# Stockwaage_Schematic_EasyEDA_ver_1_7.net
KiCad netlist of a schematic drawn in EasyEDA
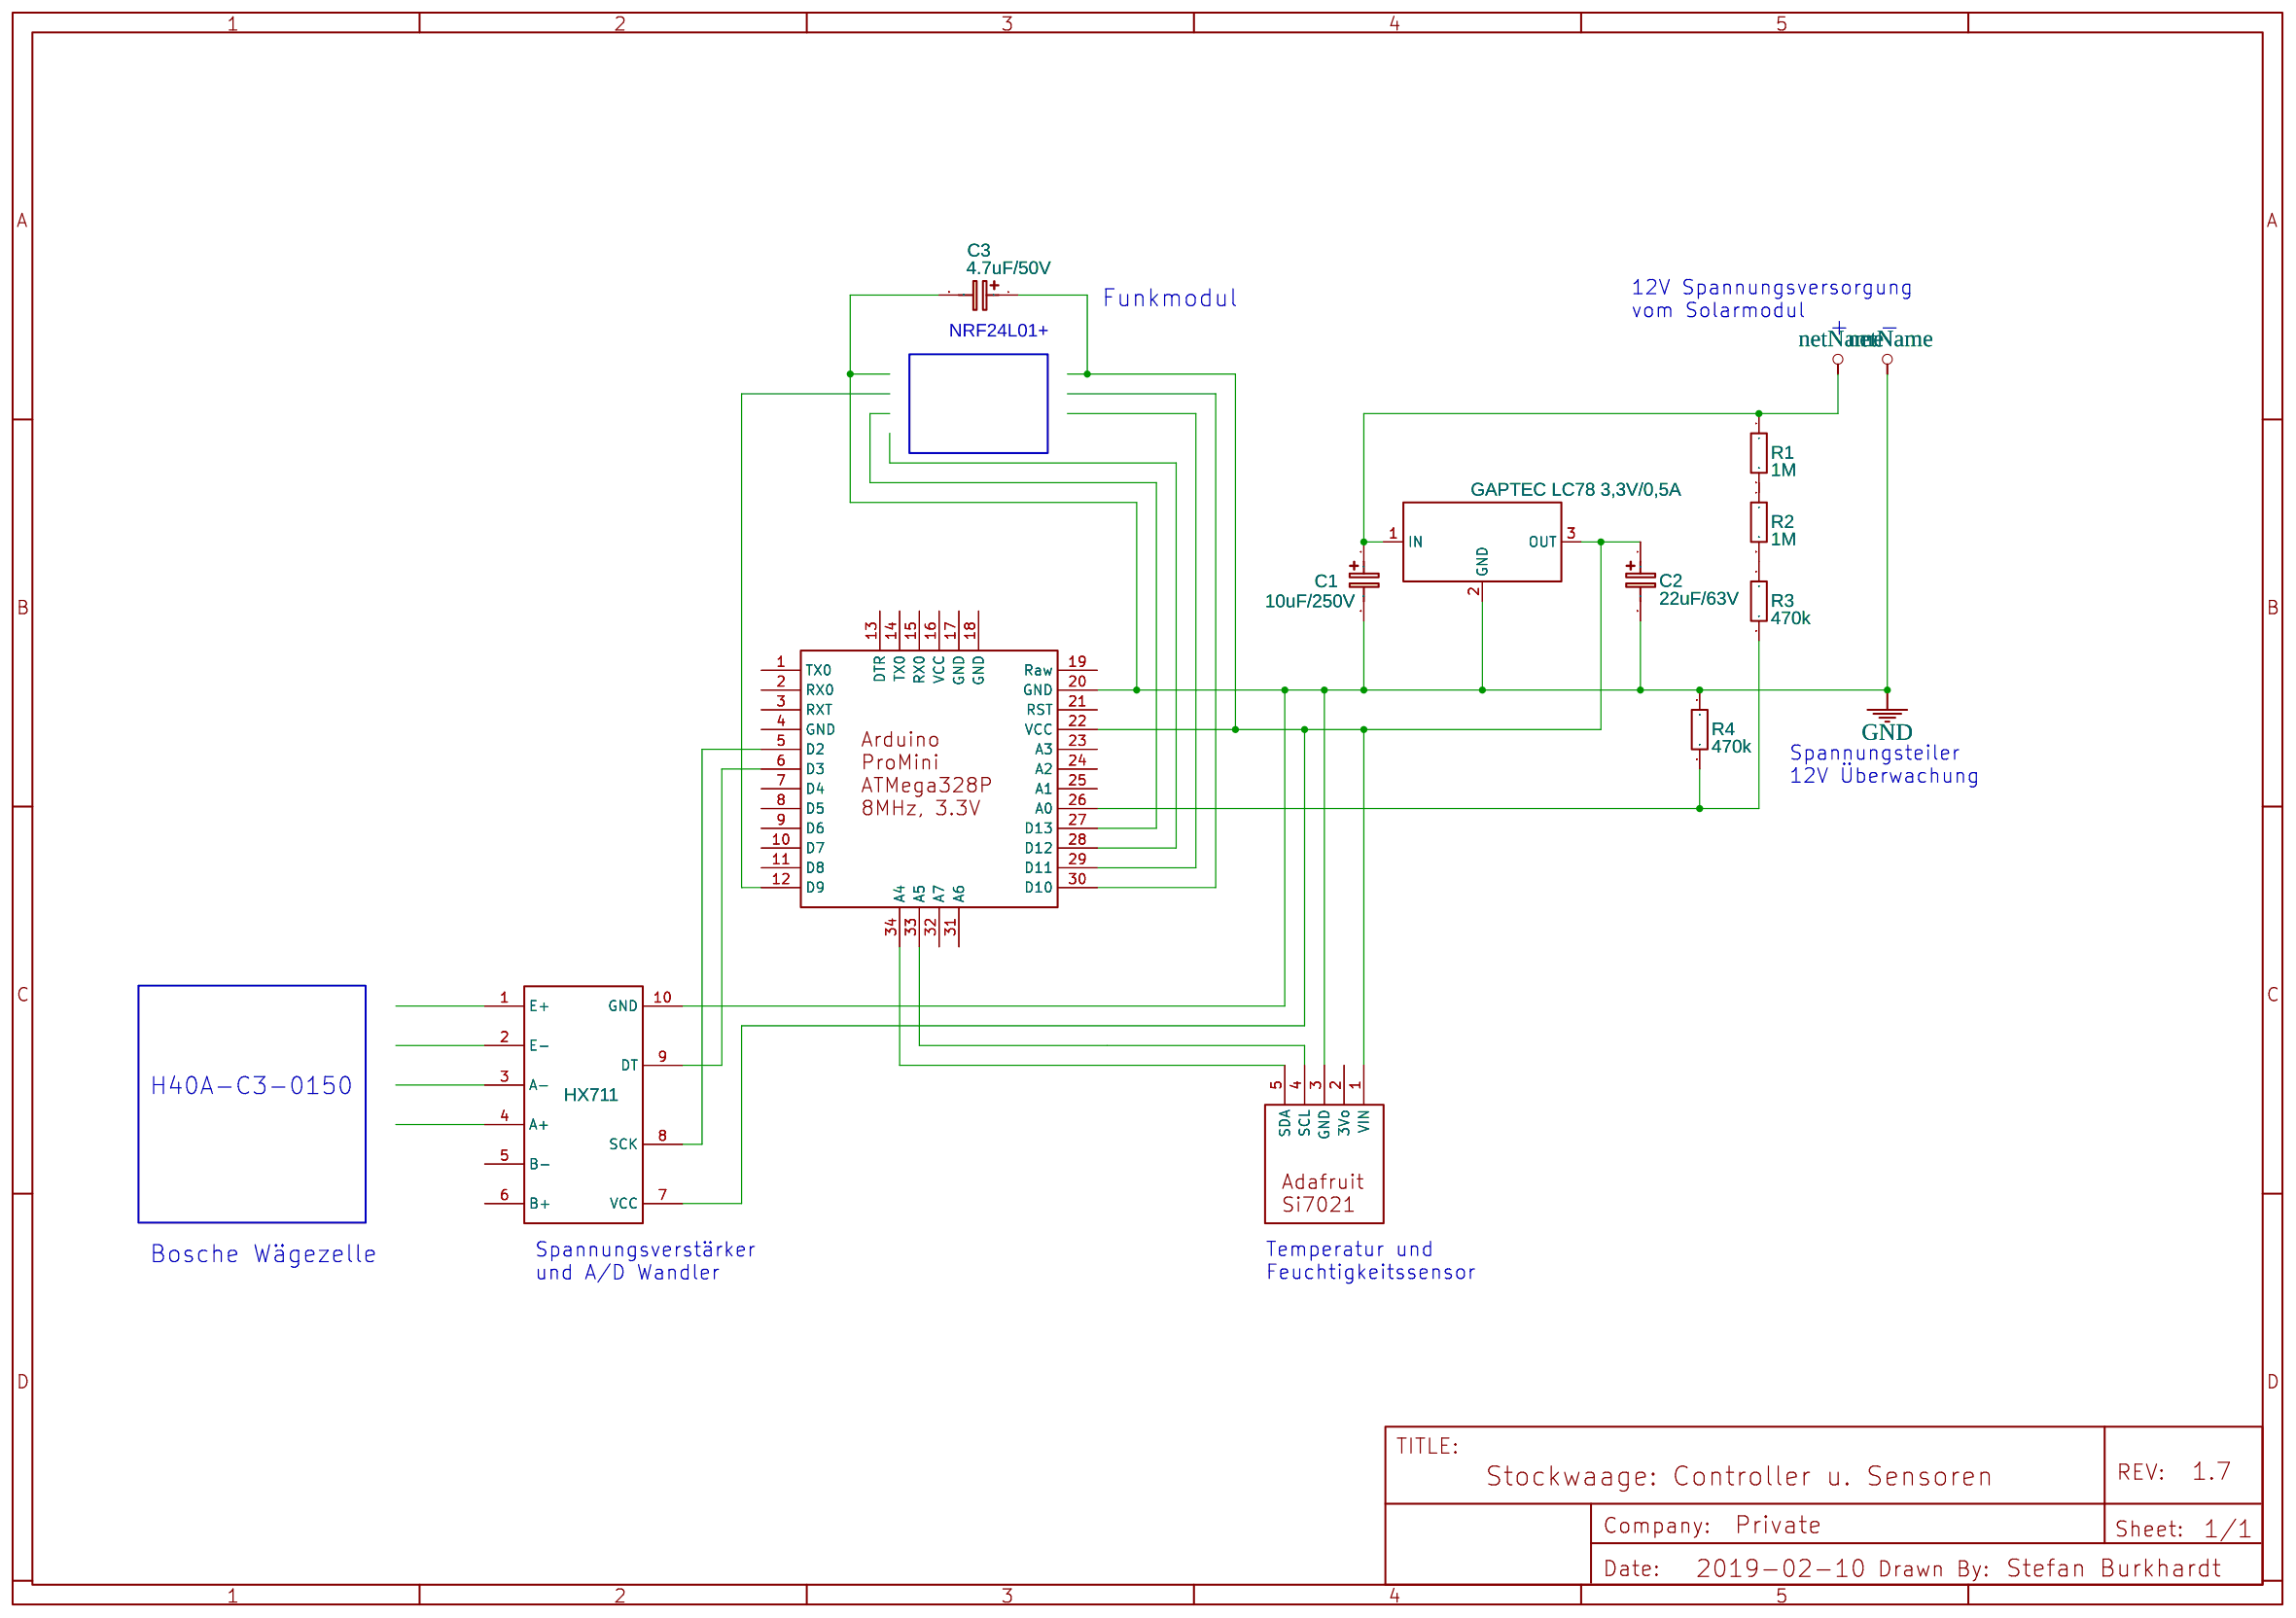
[diagram p0: schematic sheet]

(export (version "E")
  (design (tool "Eeschema 10.0.6"))
  (components
    (comp (ref "C1")
      (value "10uF/250V")
      (fields (field (name "BOM_Manufacturer Part") "?"))
      (libsource (lib "") (part "Cap_Electrolytic(TH)_D3.0XF1.5_EU"))
    )
    (comp (ref "C2")
      (value "22uF/63V")
      (fields (field (name "BOM_Manufacturer Part") "?"))
      (libsource (lib "") (part "Cap_Electrolytic(TH)_D3.0XF1.5_EU"))
    )
    (comp (ref "C3")
      (value "4.7uF/50V")
      (fields (field (name "BOM_Manufacturer Part") "?"))
      (libsource (lib "") (part "Cap_Electrolytic(TH)_D3.0XF1.5_EU_1"))
    )
    (comp (ref "R1")
      (value "1M")
      (fields (field (name "BOM_Manufacturer Part") "?"))
      (libsource (lib "") (part "Res_AXIAL-0.3(1/8W)_EU"))
    )
    (comp (ref "R2")
      (value "1M")
      (fields (field (name "BOM_Manufacturer Part") "?"))
      (libsource (lib "") (part "Res_AXIAL-0.3(1/8W)_EU"))
    )
    (comp (ref "R3")
      (value "470k")
      (fields (field (name "BOM_Manufacturer Part") "?"))
      (libsource (lib "") (part "Res_AXIAL-0.3(1/8W)_EU"))
    )
    (comp (ref "R4")
      (value "470k")
      (fields (field (name "BOM_Manufacturer Part") "?"))
      (libsource (lib "") (part "Res_AXIAL-0.3(1/8W)_EU"))
    )
    (comp (ref "U1")
      (value "Arduino ProMini ATMega328P 8MHz, 3.3V")
      (fields (field (name "BOM_Manufacturer Part") "Arduino ProMini3v3"))
      (libsource (lib "") (part "Unknown_580_380"))
    )
    (comp (ref "U2")
      (value "GAPTEC LC78 3,3V/0,5A")
      (fields (field (name "BOM_Manufacturer Part") "?"))
      (libsource (lib "") (part "Unknown_860_270"))
    )
    (comp (ref "U3")
      (value "Adafruit Si7021")
      (fields (field (name "BOM_Manufacturer Part") "?") (field (name "BOM_Supplier Part") "3251"))
      (libsource (lib "") (part "Unknown_810_555"))
    )
    (comp (ref "U5") (value "HX711") (libsource (lib "") (part "Unknown_405_545")))
  )
  (nets
    (net (code "1") (name "GND") (class "Default")
      (node (ref "C1") (pin "1") (pinfunction "1_1") (pintype "unspecified"))
      (node (ref "C1") (pin "2") (pinfunction "2_2") (pintype "unspecified"))
      (node (ref "C2") (pin "2") (pinfunction "2_2") (pintype "unspecified"))
      (node (ref "C3") (pin "2") (pinfunction "2_2") (pintype "unspecified"))
      (node (ref "R1") (pin "1") (pinfunction "1_1") (pintype "unspecified"))
      (node (ref "R4") (pin "1") (pinfunction "1_1") (pintype "unspecified"))
      (node (ref "U1") (pin "20") (pinfunction "GND_20") (pintype "unspecified"))
      (node (ref "U2") (pin "1") (pinfunction "IN_1") (pintype "unspecified"))
      (node (ref "U2") (pin "2") (pinfunction "GND_2") (pintype "unspecified"))
      (node (ref "U3") (pin "3") (pinfunction "GND_3") (pintype "unspecified"))
      (node (ref "U5") (pin "10") (pinfunction "GND_10") (pintype "unspecified"))
    )
    (net (code "2") (name "Net-(R2-Pad2)") (class "Default")
      (node (ref "R2") (pin "2") (pinfunction "2_2") (pintype "unspecified"))
      (node (ref "R3") (pin "1") (pinfunction "1_1") (pintype "unspecified"))
    )
    (net (code "3") (name "Net-(U1-A0)") (class "Default")
      (node (ref "R3") (pin "2") (pinfunction "2_2") (pintype "unspecified"))
      (node (ref "R4") (pin "2") (pinfunction "2_2") (pintype "unspecified"))
      (node (ref "U1") (pin "26") (pinfunction "A0_26") (pintype "unspecified"))
    )
    (net (code "4") (name "Net-(U1-A4)") (class "Default")
      (node (ref "U1") (pin "34") (pinfunction "A4_34") (pintype "unspecified"))
      (node (ref "U3") (pin "5") (pinfunction "SDA_5") (pintype "bidirectional"))
    )
    (net (code "5") (name "Net-(U1-A5)") (class "Default")
      (node (ref "U1") (pin "33") (pinfunction "A5_33") (pintype "unspecified"))
      (node (ref "U3") (pin "4") (pinfunction "SCL_4") (pintype "bidirectional"))
    )
    (net (code "6") (name "Net-(U1-D2)") (class "Default")
      (node (ref "U1") (pin "5") (pinfunction "D2_5") (pintype "unspecified"))
      (node (ref "U5") (pin "8") (pinfunction "SCK_8") (pintype "unspecified"))
    )
    (net (code "7") (name "Net-(U1-D3)") (class "Default")
      (node (ref "U1") (pin "6") (pinfunction "D3_6") (pintype "unspecified"))
      (node (ref "U5") (pin "9") (pinfunction "DT_9") (pintype "unspecified"))
    )
    (net (code "8") (name "Net-(U2-OUT)") (class "Default")
      (node (ref "C2") (pin "1") (pinfunction "1_1") (pintype "unspecified"))
      (node (ref "C3") (pin "1") (pinfunction "1_1") (pintype "unspecified"))
      (node (ref "U1") (pin "22") (pinfunction "VCC_22") (pintype "unspecified"))
      (node (ref "U2") (pin "3") (pinfunction "OUT_3") (pintype "unspecified"))
      (node (ref "U3") (pin "1") (pinfunction "VIN_1") (pintype "input"))
      (node (ref "U5") (pin "7") (pinfunction "VCC_7") (pintype "unspecified"))
    )
    (net (code "9") (name "unconnected-(R1-Pad2)") (class "Default")
      (node (ref "R1") (pin "2") (pinfunction "2_2") (pintype "unspecified"))
    )
    (net (code "10") (name "unconnected-(R2-Pad1)") (class "Default")
      (node (ref "R2") (pin "1") (pinfunction "1_1") (pintype "unspecified"))
    )
    (net (code "11") (name "unconnected-(U1-A1-Pad25)") (class "Default")
      (node (ref "U1") (pin "25") (pinfunction "A1_25") (pintype "unspecified"))
    )
    (net (code "12") (name "unconnected-(U1-A2-Pad24)") (class "Default")
      (node (ref "U1") (pin "24") (pinfunction "A2_24") (pintype "unspecified"))
    )
    (net (code "13") (name "unconnected-(U1-A3-Pad23)") (class "Default")
      (node (ref "U1") (pin "23") (pinfunction "A3_23") (pintype "unspecified"))
    )
    (net (code "14") (name "unconnected-(U1-A6-Pad31)") (class "Default")
      (node (ref "U1") (pin "31") (pinfunction "A6_31") (pintype "unspecified"))
    )
    (net (code "15") (name "unconnected-(U1-A7-Pad32)") (class "Default")
      (node (ref "U1") (pin "32") (pinfunction "A7_32") (pintype "unspecified"))
    )
    (net (code "16") (name "unconnected-(U1-D4-Pad7)") (class "Default")
      (node (ref "U1") (pin "7") (pinfunction "D4_7") (pintype "unspecified"))
    )
    (net (code "17") (name "unconnected-(U1-D5-Pad8)") (class "Default")
      (node (ref "U1") (pin "8") (pinfunction "D5_8") (pintype "unspecified"))
    )
    (net (code "18") (name "unconnected-(U1-D6-Pad9)") (class "Default")
      (node (ref "U1") (pin "9") (pinfunction "D6_9") (pintype "unspecified"))
    )
    (net (code "19") (name "unconnected-(U1-D7-Pad10)") (class "Default")
      (node (ref "U1") (pin "10") (pinfunction "D7_10") (pintype "unspecified"))
    )
    (net (code "20") (name "unconnected-(U1-D8-Pad11)") (class "Default")
      (node (ref "U1") (pin "11") (pinfunction "D8_11") (pintype "unspecified"))
    )
    (net (code "21") (name "unconnected-(U1-D9-Pad12)") (class "Default")
      (node (ref "U1") (pin "12") (pinfunction "D9_12") (pintype "unspecified"))
    )
    (net (code "22") (name "unconnected-(U1-D10-Pad30)") (class "Default")
      (node (ref "U1") (pin "30") (pinfunction "D10_30") (pintype "unspecified"))
    )
    (net (code "23") (name "unconnected-(U1-D11-Pad29)") (class "Default")
      (node (ref "U1") (pin "29") (pinfunction "D11_29") (pintype "unspecified"))
    )
    (net (code "24") (name "unconnected-(U1-D12-Pad28)") (class "Default")
      (node (ref "U1") (pin "28") (pinfunction "D12_28") (pintype "unspecified"))
    )
    (net (code "25") (name "unconnected-(U1-D13-Pad27)") (class "Default")
      (node (ref "U1") (pin "27") (pinfunction "D13_27") (pintype "unspecified"))
    )
    (net (code "26") (name "unconnected-(U1-DTR-Pad13)") (class "Default")
      (node (ref "U1") (pin "13") (pinfunction "DTR_13") (pintype "unspecified"))
    )
    (net (code "27") (name "unconnected-(U1-GND-Pad4)") (class "Default")
      (node (ref "U1") (pin "4") (pinfunction "GND_4") (pintype "unspecified"))
    )
    (net (code "28") (name "unconnected-(U1-GND-Pad17)") (class "Default")
      (node (ref "U1") (pin "17") (pinfunction "GND_17") (pintype "unspecified"))
    )
    (net (code "29") (name "unconnected-(U1-GND-Pad18)") (class "Default")
      (node (ref "U1") (pin "18") (pinfunction "GND_18") (pintype "unspecified"))
    )
    (net (code "30") (name "unconnected-(U1-RST-Pad21)") (class "Default")
      (node (ref "U1") (pin "21") (pinfunction "RST_21") (pintype "unspecified"))
    )
    (net (code "31") (name "unconnected-(U1-RX0-Pad2)") (class "Default")
      (node (ref "U1") (pin "2") (pinfunction "RX0_2") (pintype "unspecified"))
    )
    (net (code "32") (name "unconnected-(U1-RX0-Pad15)") (class "Default")
      (node (ref "U1") (pin "15") (pinfunction "RX0_15") (pintype "unspecified"))
    )
    (net (code "33") (name "unconnected-(U1-RXT-Pad3)") (class "Default")
      (node (ref "U1") (pin "3") (pinfunction "RXT_3") (pintype "unspecified"))
    )
    (net (code "34") (name "unconnected-(U1-Raw-Pad19)") (class "Default")
      (node (ref "U1") (pin "19") (pinfunction "Raw_19") (pintype "unspecified"))
    )
    (net (code "35") (name "unconnected-(U1-TX0-Pad1)") (class "Default")
      (node (ref "U1") (pin "1") (pinfunction "TX0_1") (pintype "unspecified"))
    )
    (net (code "36") (name "unconnected-(U1-TX0-Pad14)") (class "Default")
      (node (ref "U1") (pin "14") (pinfunction "TX0_14") (pintype "unspecified"))
    )
    (net (code "37") (name "unconnected-(U1-VCC-Pad16)") (class "Default")
      (node (ref "U1") (pin "16") (pinfunction "VCC_16") (pintype "unspecified"))
    )
    (net (code "38") (name "unconnected-(U3-3Vo-Pad2)") (class "Default")
      (node (ref "U3") (pin "2") (pinfunction "3Vo_2") (pintype "output"))
    )
    (net (code "39") (name "unconnected-(U5-A+-Pad4)") (class "Default")
      (node (ref "U5") (pin "4") (pinfunction "A+_4") (pintype "unspecified"))
    )
    (net (code "40") (name "unconnected-(U5-A--Pad3)") (class "Default")
      (node (ref "U5") (pin "3") (pinfunction "A-_3") (pintype "unspecified"))
    )
    (net (code "41") (name "unconnected-(U5-B+-Pad6)") (class "Default")
      (node (ref "U5") (pin "6") (pinfunction "B+_6") (pintype "unspecified"))
    )
    (net (code "42") (name "unconnected-(U5-B--Pad5)") (class "Default")
      (node (ref "U5") (pin "5") (pinfunction "B-_5") (pintype "unspecified"))
    )
    (net (code "43") (name "unconnected-(U5-E+-Pad1)") (class "Default")
      (node (ref "U5") (pin "1") (pinfunction "E+_1") (pintype "unspecified"))
    )
    (net (code "44") (name "unconnected-(U5-E--Pad2)") (class "Default")
      (node (ref "U5") (pin "2") (pinfunction "E-_2") (pintype "unspecified"))
    )
  )
)
